# USB0_1.net
KiCad netlist of a schematic drawn in Altium Designer
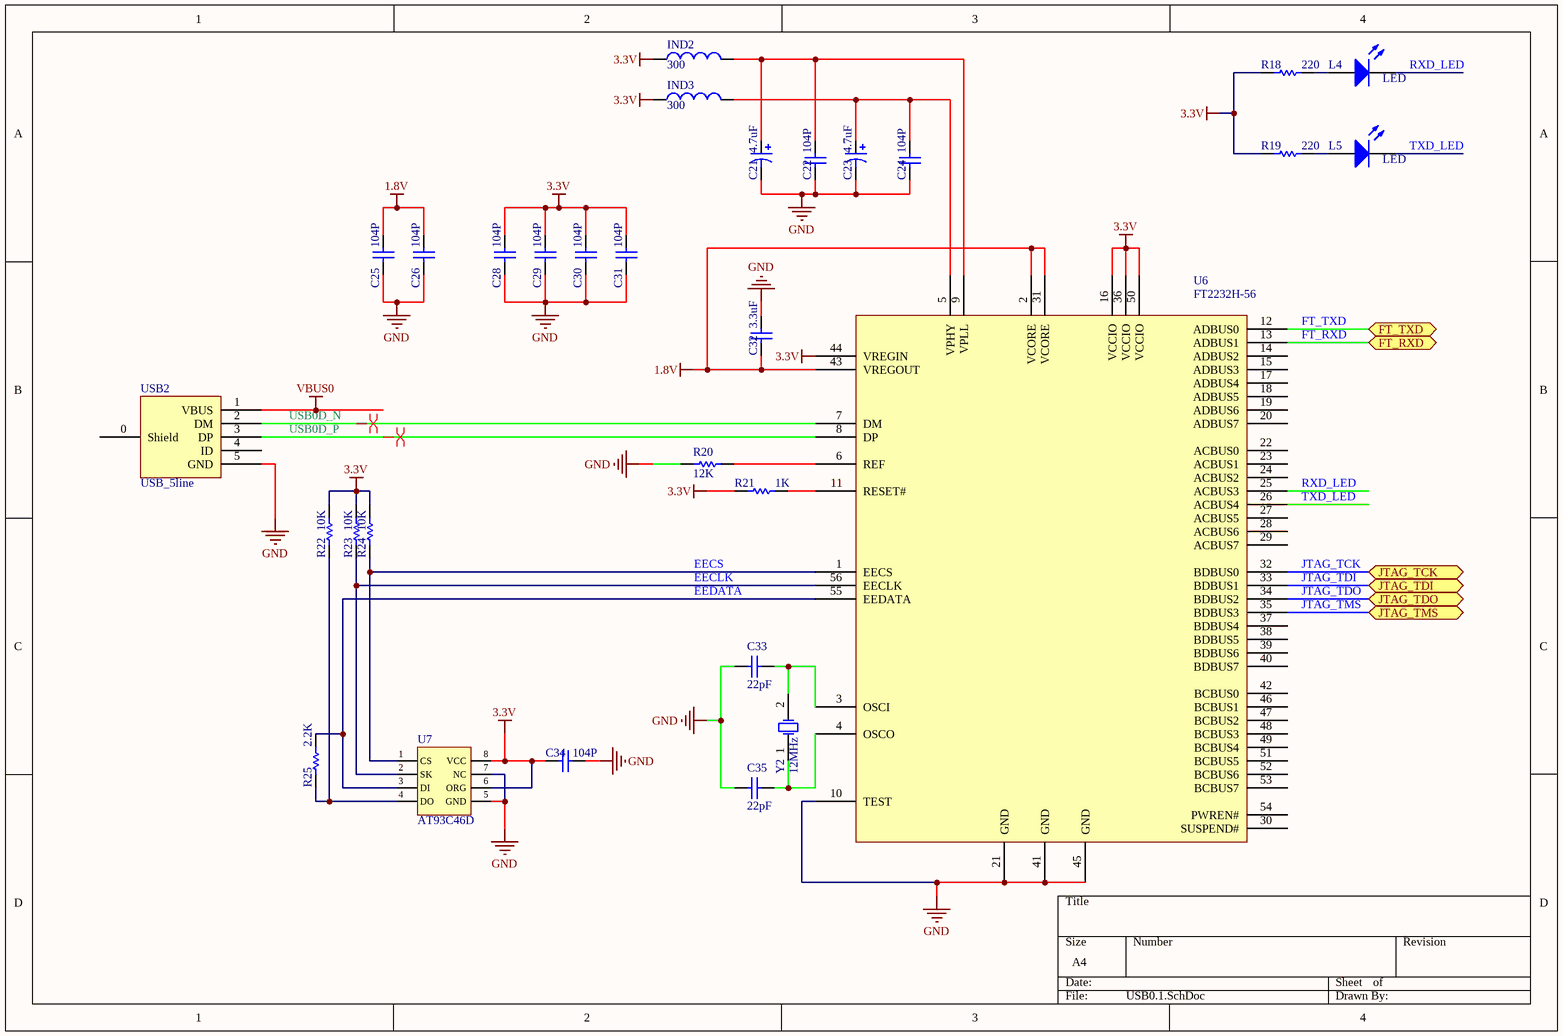
[diagram p0: USB0.1.SchDoc]

(export (version "E")
  (design (tool "Eeschema 10.0.6"))
  (components
    (comp (ref "C21")
      (value "4.7uF")
      (footprint "1608[0603]")
      (description "Polarized Capacitor (Radial)")
      (fields (field (name "Comment") "Cap Pol1") (field (name "PUBLISHER") "Altium Limited"))
      (libsource (lib "Miscellaneous Devices") (part "Cap Pol1"))
    )
    (comp (ref "C22")
      (value "104P")
      (footprint "1608[0603]")
      (description "贴片电容")
      (fields (field (name "Comment") "Cap") (field (name "PUBLISHER") "Altium Limited"))
      (libsource (lib "Sparks") (part "Cap"))
    )
    (comp (ref "C23")
      (value "4.7uF")
      (footprint "1608[0603]")
      (description "Polarized Capacitor (Radial)")
      (fields (field (name "Comment") "Cap Pol1") (field (name "PUBLISHER") "Altium Limited"))
      (libsource (lib "Miscellaneous Devices") (part "Cap Pol1"))
    )
    (comp (ref "C24")
      (value "104P")
      (footprint "1608[0603]")
      (description "贴片电容")
      (fields (field (name "Comment") "Cap") (field (name "PUBLISHER") "Altium Limited"))
      (libsource (lib "Sparks") (part "Cap"))
    )
    (comp (ref "C25")
      (value "104P")
      (footprint "1608[0603]")
      (description "贴片电容")
      (fields (field (name "Comment") "Cap") (field (name "PUBLISHER") "Altium Limited"))
      (libsource (lib "Sparks") (part "Cap"))
    )
    (comp (ref "C26")
      (value "104P")
      (footprint "1608[0603]")
      (description "贴片电容")
      (fields (field (name "Comment") "Cap") (field (name "PUBLISHER") "Altium Limited"))
      (libsource (lib "Sparks") (part "Cap"))
    )
    (comp (ref "C28")
      (value "104P")
      (footprint "1608[0603]")
      (description "贴片电容")
      (fields (field (name "Comment") "Cap") (field (name "PUBLISHER") "Altium Limited"))
      (libsource (lib "Sparks") (part "Cap"))
    )
    (comp (ref "C29")
      (value "104P")
      (footprint "1608[0603]")
      (description "贴片电容")
      (fields (field (name "Comment") "Cap") (field (name "PUBLISHER") "Altium Limited"))
      (libsource (lib "Sparks") (part "Cap"))
    )
    (comp (ref "C30")
      (value "104P")
      (footprint "1608[0603]")
      (description "贴片电容")
      (fields (field (name "Comment") "Cap") (field (name "PUBLISHER") "Altium Limited"))
      (libsource (lib "Sparks") (part "Cap"))
    )
    (comp (ref "C31")
      (value "104P")
      (footprint "1608[0603]")
      (description "贴片电容")
      (fields (field (name "Comment") "Cap") (field (name "PUBLISHER") "Altium Limited"))
      (libsource (lib "Sparks") (part "Cap"))
    )
    (comp (ref "C32")
      (value "3.3uF")
      (footprint "1608[0603]")
      (description "贴片电容")
      (fields (field (name "Comment") "Cap") (field (name "PUBLISHER") "Altium Limited"))
      (libsource (lib "Sparks") (part "Cap"))
    )
    (comp (ref "C33")
      (value "22pF")
      (footprint "1608[0603]")
      (description "贴片电容")
      (fields (field (name "Comment") "Cap") (field (name "PUBLISHER") "Altium Limited"))
      (libsource (lib "Sparks") (part "Cap"))
    )
    (comp (ref "C34")
      (value "104P")
      (footprint "1608[0603]")
      (description "贴片电容")
      (fields (field (name "Comment") "Cap") (field (name "PUBLISHER") "Altium Limited"))
      (libsource (lib "Sparks") (part "Cap"))
    )
    (comp (ref "C35")
      (value "22pF")
      (footprint "1608[0603]")
      (description "贴片电容")
      (fields (field (name "Comment") "Cap") (field (name "PUBLISHER") "Altium Limited"))
      (libsource (lib "Sparks") (part "Cap"))
    )
    (comp (ref "IND2")
      (value "300")
      (footprint "0402")
      (description "Inductor")
      (fields (field (name "PUBLISHER") "Altium Limited"))
      (libsource (lib "Miscellaneous Devices") (part "Inductor"))
    )
    (comp (ref "IND3")
      (value "300")
      (footprint "0402")
      (description "Inductor")
      (fields (field (name "PUBLISHER") "Altium Limited"))
      (libsource (lib "Miscellaneous Devices") (part "Inductor"))
    )
    (comp (ref "L4") (value "LED") (footprint "1608[0603]") (libsource (lib "Sparks") (part "LED")))
    (comp (ref "L5") (value "LED") (footprint "1608[0603]") (libsource (lib "Sparks") (part "LED")))
    (comp (ref "R18")
      (value "220")
      (footprint "1608[0603]")
      (description "贴片电阻")
      (fields (field (name "Comment") "Res") (field (name "PUBLISHER") "Altium Limited"))
      (libsource (lib "Sparks") (part "Res"))
    )
    (comp (ref "R19")
      (value "220")
      (footprint "1608[0603]")
      (description "贴片电阻")
      (fields (field (name "Comment") "Res") (field (name "PUBLISHER") "Altium Limited"))
      (libsource (lib "Sparks") (part "Res"))
    )
    (comp (ref "R20")
      (value "12K")
      (footprint "1608[0603]")
      (description "贴片电阻")
      (fields (field (name "Comment") "Res") (field (name "PUBLISHER") "Altium Limited"))
      (libsource (lib "Sparks") (part "Res"))
    )
    (comp (ref "R21")
      (value "1K")
      (footprint "1608[0603]")
      (description "贴片电阻")
      (fields (field (name "Comment") "Res") (field (name "PUBLISHER") "Altium Limited"))
      (libsource (lib "Sparks") (part "Res"))
    )
    (comp (ref "R22")
      (value "10K")
      (footprint "1608[0603]")
      (description "贴片电阻")
      (fields (field (name "Comment") "Res") (field (name "PUBLISHER") "Altium Limited"))
      (libsource (lib "Sparks") (part "Res"))
    )
    (comp (ref "R23")
      (value "10K")
      (footprint "1608[0603]")
      (description "贴片电阻")
      (fields (field (name "Comment") "Res") (field (name "PUBLISHER") "Altium Limited"))
      (libsource (lib "Sparks") (part "Res"))
    )
    (comp (ref "R24")
      (value "10K")
      (footprint "1608[0603]")
      (description "贴片电阻")
      (fields (field (name "Comment") "Res") (field (name "PUBLISHER") "Altium Limited"))
      (libsource (lib "Sparks") (part "Res"))
    )
    (comp (ref "R25")
      (value "2.2K")
      (footprint "1608[0603]")
      (description "贴片电阻")
      (fields (field (name "Comment") "Res") (field (name "PUBLISHER") "Altium Limited"))
      (libsource (lib "Sparks") (part "Res"))
    )
    (comp (ref "U6")
      (value "FT2232H-56")
      (footprint "QFN50P800X800X90_HS-57N")
      (libsource (lib "2号库") (part "FT2232H-56"))
    )
    (comp (ref "U7")
      (value "AT93C46D")
      (footprint "TSOP65P640X120-8N-AT93C46D")
      (libsource (lib "2号库") (part "AT93C46D"))
    )
    (comp (ref "USB2")
      (value "USB_5line")
      (footprint "USB-MICRO-5P-2F")
      (libsource (lib "2号库") (part "USB_5line"))
    )
    (comp (ref "Y2")
      (value "12MHz")
      (footprint "5032")
      (description "晶体振荡器")
      (fields (field (name "PUBLISHER") "Altium Limited"))
      (libsource (lib "Sparks") (part "XTAL"))
    )
  )
  (nets
    (net (code "1") (name "/EECLK") (class "Default")
      (node (ref "R23") (pin "2") (pinfunction "2_2") (pintype "passive"))
      (node (ref "U6") (pin "56") (pinfunction "EECLK_56") (pintype "passive"))
      (node (ref "U7") (pin "2") (pinfunction "SK_2") (pintype "passive"))
    )
    (net (code "2") (name "/EECS") (class "Default")
      (node (ref "R24") (pin "2") (pinfunction "2_2") (pintype "passive"))
      (node (ref "U6") (pin "1") (pinfunction "EECS_1") (pintype "passive"))
      (node (ref "U7") (pin "1") (pinfunction "CS_1") (pintype "passive"))
    )
    (net (code "3") (name "/EEDATA") (class "Default")
      (node (ref "R25") (pin "1") (pinfunction "1_1") (pintype "passive"))
      (node (ref "U6") (pin "55") (pinfunction "EEDATA_55") (pintype "passive"))
      (node (ref "U7") (pin "3") (pinfunction "DI_3") (pintype "passive"))
    )
    (net (code "4") (name "/FT_RXD") (class "Default")
      (node (ref "U6") (pin "13") (pinfunction "ADBUS1_13") (pintype "passive"))
    )
    (net (code "5") (name "/FT_TXD") (class "Default")
      (node (ref "U6") (pin "12") (pinfunction "ADBUS0_12") (pintype "passive"))
    )
    (net (code "6") (name "/JTAG_TCK") (class "Default")
      (node (ref "U6") (pin "32") (pinfunction "BDBUS0_32") (pintype "passive"))
    )
    (net (code "7") (name "/JTAG_TDI") (class "Default")
      (node (ref "U6") (pin "33") (pinfunction "BDBUS1_33") (pintype "passive"))
    )
    (net (code "8") (name "/JTAG_TDO") (class "Default")
      (node (ref "U6") (pin "34") (pinfunction "BDBUS2_34") (pintype "passive"))
    )
    (net (code "9") (name "/JTAG_TMS") (class "Default")
      (node (ref "U6") (pin "35") (pinfunction "BDBUS3_35") (pintype "passive"))
    )
    (net (code "10") (name "/RXD_LED") (class "Default")
      (node (ref "L4") (pin "2") (pinfunction "K_2") (pintype "passive"))
      (node (ref "U6") (pin "25") (pinfunction "ACBUS3_25") (pintype "passive"))
    )
    (net (code "11") (name "/TXD_LED") (class "Default")
      (node (ref "L5") (pin "2") (pinfunction "K_2") (pintype "passive"))
      (node (ref "U6") (pin "26") (pinfunction "ACBUS4_26") (pintype "passive"))
    )
    (net (code "12") (name "/USB0D_N") (class "Default")
      (node (ref "U6") (pin "7") (pinfunction "DM_7") (pintype "passive"))
      (node (ref "USB2") (pin "2") (pinfunction "DM_2") (pintype "passive"))
    )
    (net (code "13") (name "/USB0D_P") (class "Default")
      (node (ref "U6") (pin "8") (pinfunction "DP_8") (pintype "passive"))
      (node (ref "USB2") (pin "3") (pinfunction "DP_3") (pintype "passive"))
    )
    (net (code "14") (name "1.8V") (class "Default")
      (node (ref "C25") (pin "2") (pinfunction "2_2") (pintype "passive"))
      (node (ref "C26") (pin "2") (pinfunction "2_2") (pintype "passive"))
      (node (ref "C32") (pin "1") (pinfunction "1_1") (pintype "passive"))
      (node (ref "U6") (pin "2") (pinfunction "VCORE_2") (pintype "passive"))
      (node (ref "U6") (pin "31") (pinfunction "VCORE_31") (pintype "passive"))
      (node (ref "U6") (pin "43") (pinfunction "VREGOUT_43") (pintype "passive"))
    )
    (net (code "15") (name "3.3V") (class "Default")
      (node (ref "C28") (pin "2") (pinfunction "2_2") (pintype "passive"))
      (node (ref "C29") (pin "2") (pinfunction "2_2") (pintype "passive"))
      (node (ref "C30") (pin "2") (pinfunction "2_2") (pintype "passive"))
      (node (ref "C31") (pin "2") (pinfunction "2_2") (pintype "passive"))
      (node (ref "C34") (pin "2") (pinfunction "2_2") (pintype "passive"))
      (node (ref "IND2") (pin "1") (pinfunction "1_1") (pintype "passive"))
      (node (ref "IND3") (pin "1") (pinfunction "1_1") (pintype "passive"))
      (node (ref "R18") (pin "2") (pinfunction "2_2") (pintype "passive"))
      (node (ref "R19") (pin "2") (pinfunction "2_2") (pintype "passive"))
      (node (ref "R21") (pin "2") (pinfunction "2_2") (pintype "passive"))
      (node (ref "R22") (pin "1") (pinfunction "1_1") (pintype "passive"))
      (node (ref "R23") (pin "1") (pinfunction "1_1") (pintype "passive"))
      (node (ref "R24") (pin "1") (pinfunction "1_1") (pintype "passive"))
      (node (ref "U6") (pin "16") (pinfunction "VCCIO_16") (pintype "passive"))
      (node (ref "U6") (pin "36") (pinfunction "VCCIO_36") (pintype "passive"))
      (node (ref "U6") (pin "44") (pinfunction "VREGIN_44") (pintype "passive"))
      (node (ref "U6") (pin "50") (pinfunction "VCCIO_50") (pintype "passive"))
      (node (ref "U7") (pin "6") (pinfunction "ORG_6") (pintype "passive"))
      (node (ref "U7") (pin "8") (pinfunction "VCC_8") (pintype "passive"))
    )
    (net (code "16") (name "GND") (class "Default")
      (node (ref "C21") (pin "2") (pinfunction "2_2") (pintype "passive"))
      (node (ref "C22") (pin "1") (pinfunction "1_1") (pintype "passive"))
      (node (ref "C23") (pin "2") (pinfunction "2_2") (pintype "passive"))
      (node (ref "C24") (pin "1") (pinfunction "1_1") (pintype "passive"))
      (node (ref "C25") (pin "1") (pinfunction "1_1") (pintype "passive"))
      (node (ref "C26") (pin "1") (pinfunction "1_1") (pintype "passive"))
      (node (ref "C28") (pin "1") (pinfunction "1_1") (pintype "passive"))
      (node (ref "C29") (pin "1") (pinfunction "1_1") (pintype "passive"))
      (node (ref "C30") (pin "1") (pinfunction "1_1") (pintype "passive"))
      (node (ref "C31") (pin "1") (pinfunction "1_1") (pintype "passive"))
      (node (ref "C32") (pin "2") (pinfunction "2_2") (pintype "passive"))
      (node (ref "C33") (pin "1") (pinfunction "1_1") (pintype "passive"))
      (node (ref "C34") (pin "1") (pinfunction "1_1") (pintype "passive"))
      (node (ref "C35") (pin "2") (pinfunction "2_2") (pintype "passive"))
      (node (ref "R20") (pin "2") (pinfunction "2_2") (pintype "passive"))
      (node (ref "U6") (pin "10") (pinfunction "TEST_10") (pintype "passive"))
      (node (ref "U6") (pin "21") (pinfunction "GND_21") (pintype "passive"))
      (node (ref "U6") (pin "41") (pinfunction "GND_41") (pintype "passive"))
      (node (ref "U6") (pin "45") (pinfunction "GND_45") (pintype "passive"))
      (node (ref "U7") (pin "5") (pinfunction "GND_5") (pintype "passive"))
      (node (ref "U7") (pin "7") (pinfunction "NC_7") (pintype "passive"))
      (node (ref "USB2") (pin "5") (pinfunction "GND_5") (pintype "passive"))
    )
    (net (code "17") (name "Net-(L4-A)") (class "Default")
      (node (ref "L4") (pin "1") (pinfunction "A_1") (pintype "passive"))
      (node (ref "R18") (pin "1") (pinfunction "1_1") (pintype "passive"))
    )
    (net (code "18") (name "Net-(L5-A)") (class "Default")
      (node (ref "L5") (pin "1") (pinfunction "A_1") (pintype "passive"))
      (node (ref "R19") (pin "1") (pinfunction "1_1") (pintype "passive"))
    )
    (net (code "19") (name "Net-(U6-OSCI)") (class "Default")
      (node (ref "C33") (pin "2") (pinfunction "2_2") (pintype "passive"))
      (node (ref "U6") (pin "3") (pinfunction "OSCI_3") (pintype "passive"))
      (node (ref "Y2") (pin "2") (pinfunction "OSC2_2") (pintype "passive"))
    )
    (net (code "20") (name "Net-(U6-OSCO)") (class "Default")
      (node (ref "C35") (pin "1") (pinfunction "1_1") (pintype "passive"))
      (node (ref "U6") (pin "4") (pinfunction "OSCO_4") (pintype "passive"))
      (node (ref "Y2") (pin "1") (pinfunction "OSC1_1") (pintype "passive"))
    )
    (net (code "21") (name "Net-(U6-REF)") (class "Default")
      (node (ref "R20") (pin "1") (pinfunction "1_1") (pintype "passive"))
      (node (ref "U6") (pin "6") (pinfunction "REF_6") (pintype "passive"))
    )
    (net (code "22") (name "Net-(U6-RESET#)") (class "Default")
      (node (ref "R21") (pin "1") (pinfunction "1_1") (pintype "passive"))
      (node (ref "U6") (pin "11") (pinfunction "RESET#_11") (pintype "passive"))
    )
    (net (code "23") (name "Net-(U6-VPHY)") (class "Default")
      (node (ref "C23") (pin "1") (pinfunction "1_1") (pintype "passive"))
      (node (ref "C24") (pin "2") (pinfunction "2_2") (pintype "passive"))
      (node (ref "IND3") (pin "2") (pinfunction "2_2") (pintype "passive"))
      (node (ref "U6") (pin "5") (pinfunction "VPHY_5") (pintype "passive"))
    )
    (net (code "24") (name "Net-(U6-VPLL)") (class "Default")
      (node (ref "C21") (pin "1") (pinfunction "1_1") (pintype "passive"))
      (node (ref "C22") (pin "2") (pinfunction "2_2") (pintype "passive"))
      (node (ref "IND2") (pin "2") (pinfunction "2_2") (pintype "passive"))
      (node (ref "U6") (pin "9") (pinfunction "VPLL_9") (pintype "passive"))
    )
    (net (code "25") (name "Net-(U7-DO)") (class "Default")
      (node (ref "R22") (pin "2") (pinfunction "2_2") (pintype "passive"))
      (node (ref "R25") (pin "2") (pinfunction "2_2") (pintype "passive"))
      (node (ref "U7") (pin "4") (pinfunction "DO_4") (pintype "passive"))
    )
    (net (code "26") (name "VBUS0") (class "Default")
      (node (ref "USB2") (pin "1") (pinfunction "VBUS_1") (pintype "passive"))
    )
    (net (code "27") (name "unconnected-(U6-ACBUS0-Pad22)") (class "Default")
      (node (ref "U6") (pin "22") (pinfunction "ACBUS0_22") (pintype "passive"))
    )
    (net (code "28") (name "unconnected-(U6-ACBUS1-Pad23)") (class "Default")
      (node (ref "U6") (pin "23") (pinfunction "ACBUS1_23") (pintype "passive"))
    )
    (net (code "29") (name "unconnected-(U6-ACBUS2-Pad24)") (class "Default")
      (node (ref "U6") (pin "24") (pinfunction "ACBUS2_24") (pintype "passive"))
    )
    (net (code "30") (name "unconnected-(U6-ACBUS5-Pad27)") (class "Default")
      (node (ref "U6") (pin "27") (pinfunction "ACBUS5_27") (pintype "passive"))
    )
    (net (code "31") (name "unconnected-(U6-ACBUS6-Pad28)") (class "Default")
      (node (ref "U6") (pin "28") (pinfunction "ACBUS6_28") (pintype "passive"))
    )
    (net (code "32") (name "unconnected-(U6-ACBUS7-Pad29)") (class "Default")
      (node (ref "U6") (pin "29") (pinfunction "ACBUS7_29") (pintype "passive"))
    )
    (net (code "33") (name "unconnected-(U6-ADBUS2-Pad14)") (class "Default")
      (node (ref "U6") (pin "14") (pinfunction "ADBUS2_14") (pintype "passive"))
    )
    (net (code "34") (name "unconnected-(U6-ADBUS3-Pad15)") (class "Default")
      (node (ref "U6") (pin "15") (pinfunction "ADBUS3_15") (pintype "passive"))
    )
    (net (code "35") (name "unconnected-(U6-ADBUS4-Pad17)") (class "Default")
      (node (ref "U6") (pin "17") (pinfunction "ADBUS4_17") (pintype "passive"))
    )
    (net (code "36") (name "unconnected-(U6-ADBUS5-Pad18)") (class "Default")
      (node (ref "U6") (pin "18") (pinfunction "ADBUS5_18") (pintype "passive"))
    )
    (net (code "37") (name "unconnected-(U6-ADBUS6-Pad19)") (class "Default")
      (node (ref "U6") (pin "19") (pinfunction "ADBUS6_19") (pintype "passive"))
    )
    (net (code "38") (name "unconnected-(U6-ADBUS7-Pad20)") (class "Default")
      (node (ref "U6") (pin "20") (pinfunction "ADBUS7_20") (pintype "passive"))
    )
    (net (code "39") (name "unconnected-(U6-BCBUS0-Pad42)") (class "Default")
      (node (ref "U6") (pin "42") (pinfunction "BCBUS0_42") (pintype "passive"))
    )
    (net (code "40") (name "unconnected-(U6-BCBUS1-Pad46)") (class "Default")
      (node (ref "U6") (pin "46") (pinfunction "BCBUS1_46") (pintype "passive"))
    )
    (net (code "41") (name "unconnected-(U6-BCBUS2-Pad47)") (class "Default")
      (node (ref "U6") (pin "47") (pinfunction "BCBUS2_47") (pintype "passive"))
    )
    (net (code "42") (name "unconnected-(U6-BCBUS3-Pad48)") (class "Default")
      (node (ref "U6") (pin "48") (pinfunction "BCBUS3_48") (pintype "passive"))
    )
    (net (code "43") (name "unconnected-(U6-BCBUS4-Pad49)") (class "Default")
      (node (ref "U6") (pin "49") (pinfunction "BCBUS4_49") (pintype "passive"))
    )
    (net (code "44") (name "unconnected-(U6-BCBUS5-Pad51)") (class "Default")
      (node (ref "U6") (pin "51") (pinfunction "BCBUS5_51") (pintype "passive"))
    )
    (net (code "45") (name "unconnected-(U6-BCBUS6-Pad52)") (class "Default")
      (node (ref "U6") (pin "52") (pinfunction "BCBUS6_52") (pintype "passive"))
    )
    (net (code "46") (name "unconnected-(U6-BCBUS7-Pad53)") (class "Default")
      (node (ref "U6") (pin "53") (pinfunction "BCBUS7_53") (pintype "passive"))
    )
    (net (code "47") (name "unconnected-(U6-BDBUS4-Pad37)") (class "Default")
      (node (ref "U6") (pin "37") (pinfunction "BDBUS4_37") (pintype "passive"))
    )
    (net (code "48") (name "unconnected-(U6-BDBUS5-Pad38)") (class "Default")
      (node (ref "U6") (pin "38") (pinfunction "BDBUS5_38") (pintype "passive"))
    )
    (net (code "49") (name "unconnected-(U6-BDBUS6-Pad39)") (class "Default")
      (node (ref "U6") (pin "39") (pinfunction "BDBUS6_39") (pintype "passive"))
    )
    (net (code "50") (name "unconnected-(U6-BDBUS7-Pad40)") (class "Default")
      (node (ref "U6") (pin "40") (pinfunction "BDBUS7_40") (pintype "passive"))
    )
    (net (code "51") (name "unconnected-(U6-PWREN#-Pad54)") (class "Default")
      (node (ref "U6") (pin "54") (pinfunction "PWREN#_54") (pintype "passive"))
    )
    (net (code "52") (name "unconnected-(U6-SUSPEND#-Pad30)") (class "Default")
      (node (ref "U6") (pin "30") (pinfunction "SUSPEND#_30") (pintype "passive"))
    )
    (net (code "53") (name "unconnected-(USB2-ID-Pad4)") (class "Default")
      (node (ref "USB2") (pin "4") (pinfunction "ID_4") (pintype "passive"))
    )
    (net (code "54") (name "unconnected-(USB2-Shield-Pad0)") (class "Default")
      (node (ref "USB2") (pin "0") (pinfunction "Shield_0") (pintype "passive"))
    )
  )
)
